# Power.net
KiCad netlist of a schematic drawn in Altium Designer
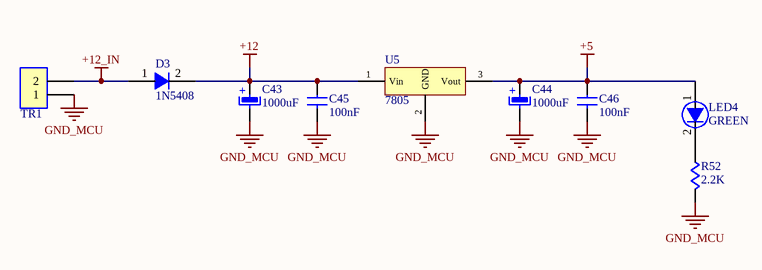
[diagram p0: Power.SchDoc]

(export (version "E")
  (design (tool "Eeschema 10.0.6"))
  (components
    (comp (ref "C43")
      (value "1000uF")
      (footprint "CAP-Elec-10x25-5")
      (description "CAPACITOR")
      (fields
        (field (name "VOLTAGE") "25V")
        (field (name "Comment") "CAP Elec 1000uF-25V-10x25-THD")
        (field (name "PUBLISHER") "Mahdi Bagherzadeh")
      )
      (libsource (lib "Mahdi-Bagherzadeh") (part "CAP-ELEC"))
    )
    (comp (ref "C44")
      (value "1000uF")
      (footprint "cap-Elec-5x7")
      (description "CAPACITOR")
      (fields
        (field (name "VOLTAGE") "10V")
        (field (name "Comment") "CAP Elec 1000uF-10V-5x7mm-THD")
        (field (name "PUBLISHER") "Mahdi Bagherzadeh")
      )
      (libsource (lib "Mahdi-Bagherzadeh") (part "CAP-ELEC"))
    )
    (comp (ref "C45")
      (value "100nF")
      (footprint "C-0805")
      (description "CAPACITOR")
      (fields
        (field (name "VOLTAGE") "50V")
        (field (name "TOLERANCE") "X7R")
        (field (name "PUBLISHER") "Mahdi Bagherzadeh")
      )
      (libsource (lib "Mahdi-Bagherzadeh") (part "CAP-CER"))
    )
    (comp (ref "C46")
      (value "100nF")
      (footprint "C-0805")
      (description "CAPACITOR")
      (fields
        (field (name "VOLTAGE") "50V")
        (field (name "TOLERANCE") "X7R")
        (field (name "PUBLISHER") "Mahdi Bagherzadeh")
      )
      (libsource (lib "Mahdi-Bagherzadeh") (part "CAP-CER"))
    )
    (comp (ref "D3")
      (value "Diode 1N5408-SMD")
      (footprint "D-DO214")
      (description "DIODE")
      (fields (field (name "CODE") "1N5408") (field (name "PUBLISHER") "Mahdi Bagherzadeh"))
      (libsource (lib "Mahdi-Bagherzadeh") (part "DIODE"))
    )
    (comp (ref "LED4")
      (value "LED GREEN-1206-SMD")
      (footprint "LED-1206-Y")
      (description "LED")
      (fields (field (name "COLOR") "GREEN") (field (name "PUBLISHER") "Mahdi Bagherzadeh"))
      (libsource (lib "Mahdi-Bagherzadeh") (part "LED"))
    )
    (comp (ref "R52")
      (value "2.2K")
      (footprint "R-0805")
      (description "RESISTOR")
      (fields
        (field (name "TOLERANCE") "5%")
        (field (name "POWER") "1/8W")
        (field (name "PUBLISHER") "Mahdi Bagherzadeh")
      )
      (libsource (lib "Mahdi-Bagherzadeh") (part "RES"))
    )
    (comp (ref "TR1")
      (value "Terminal KF301-2Pin-5.08mm-Straight")
      (footprint "KF301-2pin")
      (description "TERMINAL")
      (fields (field (name "PUBLISHER") "Mahdi Bagherzadeh"))
      (libsource (lib "Mahdi-Bagherzadeh") (part "TEMINAL-2pin"))
    )
    (comp (ref "U5")
      (value "Reg 7805-5V-THD")
      (footprint "TO220-HEARSINK-1")
      (description "REGULATOR")
      (fields
        (field (name "VOLTAGE") "5V")
        (field (name "CODE") "7805")
        (field (name "PUBLISHER") "Mahdi Bagherzadeh")
      )
      (libsource (lib "Mahdi-Bagherzadeh") (part "78Mxx"))
    )
  )
  (nets
    (net (code "1") (name "+5") (class "Default")
      (node (ref "C44") (pin "1") (pinfunction "1_1") (pintype "passive"))
      (node (ref "C46") (pin "1") (pinfunction "1_1") (pintype "passive"))
      (node (ref "LED4") (pin "1") (pinfunction "A_1") (pintype "passive"))
      (node (ref "U5") (pin "3") (pinfunction "Vout_3") (pintype "power_in"))
    )
    (net (code "2") (name "+12") (class "Default")
      (node (ref "C43") (pin "1") (pinfunction "1_1") (pintype "passive"))
      (node (ref "C45") (pin "1") (pinfunction "1_1") (pintype "passive"))
      (node (ref "D3") (pin "2") (pinfunction "C_2") (pintype "passive"))
      (node (ref "U5") (pin "1") (pinfunction "Vin_1") (pintype "power_in"))
    )
    (net (code "3") (name "+12_IN") (class "Default")
      (node (ref "D3") (pin "1") (pinfunction "A_1") (pintype "passive"))
      (node (ref "TR1") (pin "2") (pinfunction "2_2") (pintype "passive"))
    )
    (net (code "4") (name "GND_MCU") (class "Default")
      (node (ref "C43") (pin "2") (pinfunction "2_2") (pintype "passive"))
      (node (ref "C44") (pin "2") (pinfunction "2_2") (pintype "passive"))
      (node (ref "C45") (pin "2") (pinfunction "2_2") (pintype "passive"))
      (node (ref "C46") (pin "2") (pinfunction "2_2") (pintype "passive"))
      (node (ref "R52") (pin "2") (pinfunction "2_2") (pintype "passive"))
      (node (ref "TR1") (pin "1") (pinfunction "1_1") (pintype "passive"))
      (node (ref "U5") (pin "2") (pinfunction "GND_2") (pintype "power_in"))
    )
    (net (code "5") (name "Net-(LED4-C)") (class "Default")
      (node (ref "LED4") (pin "2") (pinfunction "C_2") (pintype "passive"))
      (node (ref "R52") (pin "1") (pinfunction "1_1") (pintype "passive"))
    )
  )
)
